# MCU.net
KiCad netlist of a schematic drawn in Altium Designer
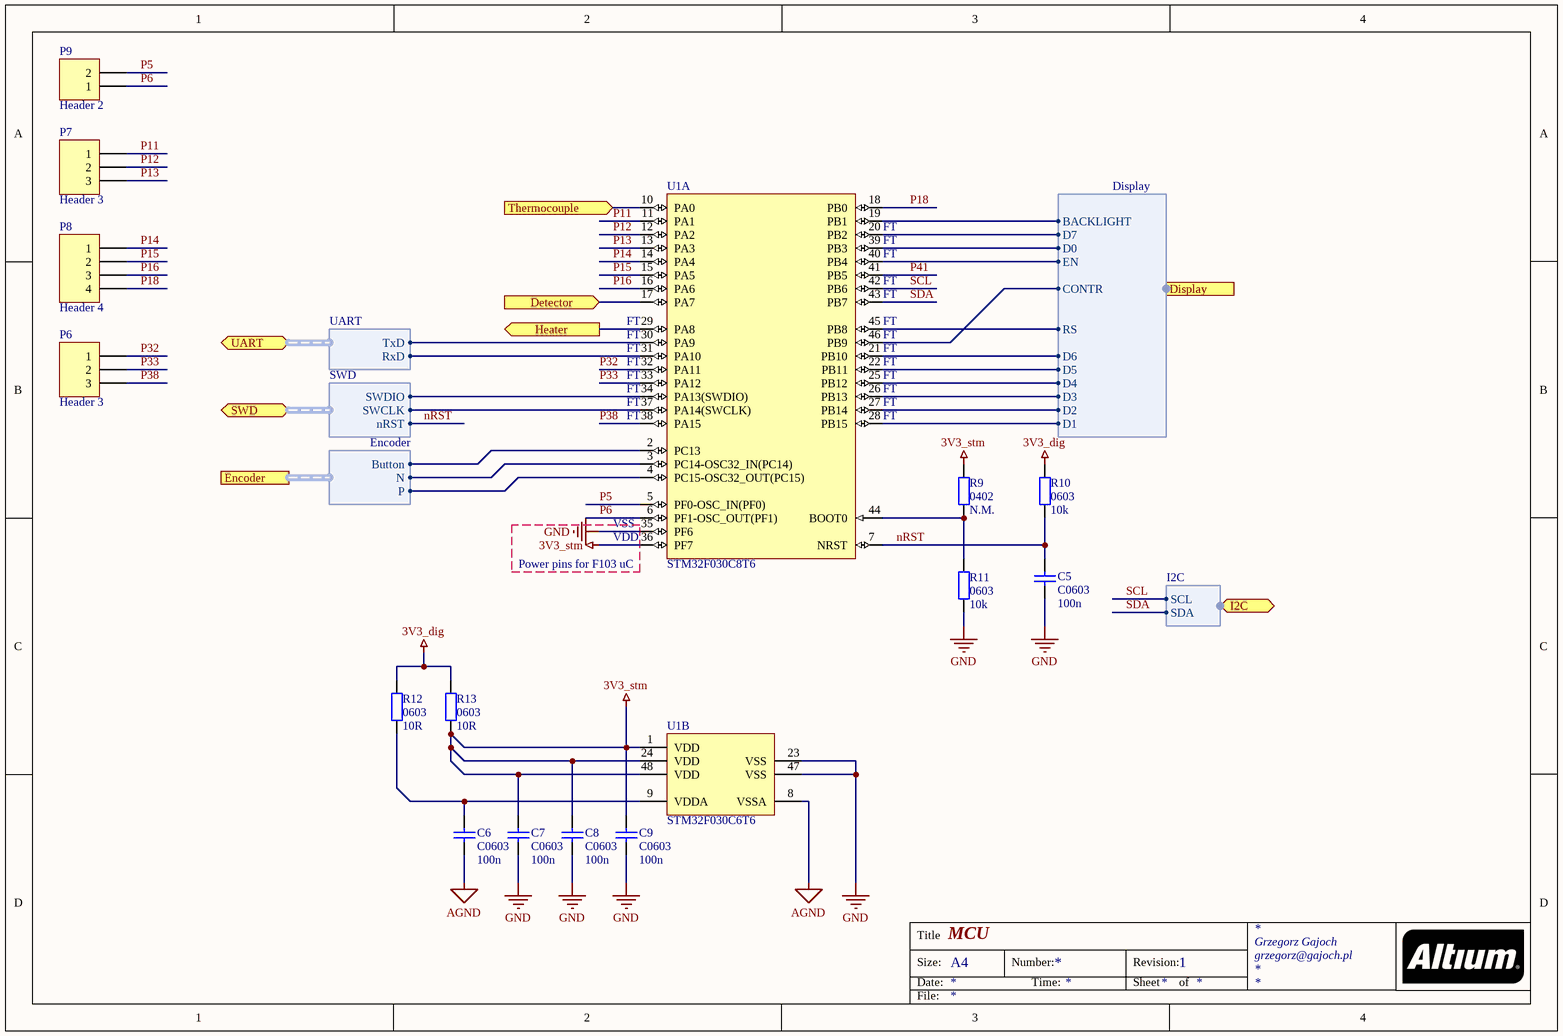
[diagram p0: MCU.SchDoc]

(export (version "E")
  (design (tool "Eeschema 10.0.6"))
  (components
    (comp (ref "C5")
      (value "100n")
      (footprint "C0603")
      (description "Generic capacitor")
      (libsource (lib "_RLC") (part "Cap"))
    )
    (comp (ref "C6")
      (value "100n")
      (footprint "C0603")
      (description "Generic capacitor")
      (libsource (lib "_RLC") (part "Cap"))
    )
    (comp (ref "C7")
      (value "100n")
      (footprint "C0603")
      (description "Generic capacitor")
      (libsource (lib "_RLC") (part "Cap"))
    )
    (comp (ref "C8")
      (value "100n")
      (footprint "C0603")
      (description "Generic capacitor")
      (libsource (lib "_RLC") (part "Cap"))
    )
    (comp (ref "C9")
      (value "100n")
      (footprint "C0603")
      (description "Generic capacitor")
      (libsource (lib "_RLC") (part "Cap"))
    )
    (comp (ref "P6")
      (value "Header 3")
      (footprint "HEADER 1X3 MALE")
      (description "Header, 3-Pin")
      (fields (field (name "PUBLISHER") "Altium Limited"))
      (libsource (lib "_Connectors") (part "Header 3"))
    )
    (comp (ref "P7")
      (value "Header 3")
      (footprint "HEADER 1X3 MALE")
      (description "Header, 3-Pin")
      (fields (field (name "PUBLISHER") "Altium Limited"))
      (libsource (lib "_Connectors") (part "Header 3"))
    )
    (comp (ref "P8")
      (value "Header 4")
      (footprint "HEADER 1x4 MALE")
      (description "Header, 4-Pin")
      (fields (field (name "PUBLISHER") "Altium Limited"))
      (libsource (lib "_Connectors") (part "Header 4"))
    )
    (comp (ref "P9")
      (value "Header 2")
      (footprint "HEADER 1X2 Male")
      (description "Header, 2-Pin")
      (fields (field (name "PUBLISHER") "Altium Limited"))
      (libsource (lib "_Connectors") (part "Header 2"))
    )
    (comp (ref "R9")
      (value "N.M.")
      (footprint "0402")
      (description "Generic resistor")
      (libsource (lib "_RLC") (part "Res"))
    )
    (comp (ref "R10")
      (value "10k")
      (footprint "0603")
      (description "Generic resistor")
      (libsource (lib "_RLC") (part "Res"))
    )
    (comp (ref "R11")
      (value "10k")
      (footprint "0603")
      (description "Generic resistor")
      (libsource (lib "_RLC") (part "Res"))
    )
    (comp (ref "R12")
      (value "10R")
      (footprint "0603")
      (description "Generic resistor")
      (libsource (lib "_RLC") (part "Res"))
    )
    (comp (ref "R13")
      (value "10R")
      (footprint "0603")
      (description "Generic resistor")
      (libsource (lib "_RLC") (part "Res"))
    )
    (comp (ref "U1")
      (value "STM32F030C8T6")
      (footprint "QFP_48_0.5_M")
      (fields (field (name "PARTNUMBER") "STM32F030C6T6"))
      (libsource (lib "_Microcircuits") (part "STM32F030C6T6"))
    )
  )
  (nets
    (net (code "6") (name "/BACKLIGHT") (class "Default")
      (node (ref "U1") (pin "19") (pinfunction "PB1_19") (pintype "bidirectional"))
    )
    (net (code "7") (name "/Button") (class "Default")
      (node (ref "U1") (pin "2") (pinfunction "PC13_2") (pintype "bidirectional"))
    )
    (net (code "8") (name "/CONTR") (class "Default")
      (node (ref "U1") (pin "46") (pinfunction "PB9_46") (pintype "bidirectional"))
    )
    (net (code "9") (name "/D0") (class "Default")
      (node (ref "U1") (pin "39") (pinfunction "PB3_39") (pintype "bidirectional"))
    )
    (net (code "10") (name "/D1") (class "Default")
      (node (ref "U1") (pin "28") (pinfunction "PB15_28") (pintype "bidirectional"))
    )
    (net (code "11") (name "/D2") (class "Default")
      (node (ref "U1") (pin "27") (pinfunction "PB14_27") (pintype "bidirectional"))
    )
    (net (code "12") (name "/D3") (class "Default")
      (node (ref "U1") (pin "26") (pinfunction "PB13_26") (pintype "bidirectional"))
    )
    (net (code "13") (name "/D4") (class "Default")
      (node (ref "U1") (pin "25") (pinfunction "PB12_25") (pintype "bidirectional"))
    )
    (net (code "14") (name "/D5") (class "Default")
      (node (ref "U1") (pin "22") (pinfunction "PB11_22") (pintype "bidirectional"))
    )
    (net (code "15") (name "/D6") (class "Default")
      (node (ref "U1") (pin "21") (pinfunction "PB10_21") (pintype "bidirectional"))
    )
    (net (code "16") (name "/D7") (class "Default")
      (node (ref "U1") (pin "20") (pinfunction "PB2_20") (pintype "bidirectional"))
    )
    (net (code "17") (name "/Detector") (class "Default")
      (node (ref "U1") (pin "17") (pinfunction "PA7_17") (pintype "bidirectional"))
    )
    (net (code "18") (name "/EN") (class "Default")
      (node (ref "U1") (pin "40") (pinfunction "PB4_40") (pintype "bidirectional"))
    )
    (net (code "19") (name "/Heater") (class "Default")
      (node (ref "U1") (pin "29") (pinfunction "PA8_29") (pintype "bidirectional"))
    )
    (net (code "20") (name "/N") (class "Default")
      (node (ref "U1") (pin "3") (pinfunction "PC14-OSC32_IN(PC14)_3") (pintype "bidirectional"))
    )
    (net (code "21") (name "/P") (class "Default")
      (node (ref "U1") (pin "4") (pinfunction "PC15-OSC32_OUT(PC15)_4") (pintype "bidirectional"))
    )
    (net (code "22") (name "/P5") (class "Default")
      (node (ref "P9") (pin "2") (pinfunction "2_2") (pintype "passive"))
      (node (ref "U1") (pin "5") (pinfunction "PF0-OSC_IN(PF0)_5") (pintype "bidirectional"))
    )
    (net (code "23") (name "/P6") (class "Default")
      (node (ref "P9") (pin "1") (pinfunction "1_1") (pintype "passive"))
      (node (ref "U1") (pin "6") (pinfunction "PF1-OSC_OUT(PF1)_6") (pintype "bidirectional"))
    )
    (net (code "24") (name "/P11") (class "Default")
      (node (ref "P7") (pin "1") (pinfunction "1_1") (pintype "passive"))
      (node (ref "U1") (pin "11") (pinfunction "PA1_11") (pintype "bidirectional"))
    )
    (net (code "25") (name "/P12") (class "Default")
      (node (ref "P7") (pin "2") (pinfunction "2_2") (pintype "passive"))
      (node (ref "U1") (pin "12") (pinfunction "PA2_12") (pintype "bidirectional"))
    )
    (net (code "26") (name "/P13") (class "Default")
      (node (ref "P7") (pin "3") (pinfunction "3_3") (pintype "passive"))
      (node (ref "U1") (pin "13") (pinfunction "PA3_13") (pintype "bidirectional"))
    )
    (net (code "27") (name "/P14") (class "Default")
      (node (ref "P8") (pin "1") (pinfunction "1_1") (pintype "passive"))
      (node (ref "U1") (pin "14") (pinfunction "PA4_14") (pintype "bidirectional"))
    )
    (net (code "28") (name "/P15") (class "Default")
      (node (ref "P8") (pin "2") (pinfunction "2_2") (pintype "passive"))
      (node (ref "U1") (pin "15") (pinfunction "PA5_15") (pintype "bidirectional"))
    )
    (net (code "29") (name "/P16") (class "Default")
      (node (ref "P8") (pin "3") (pinfunction "3_3") (pintype "passive"))
      (node (ref "U1") (pin "16") (pinfunction "PA6_16") (pintype "bidirectional"))
    )
    (net (code "30") (name "/P18") (class "Default")
      (node (ref "P8") (pin "4") (pinfunction "4_4") (pintype "passive"))
      (node (ref "U1") (pin "18") (pinfunction "PB0_18") (pintype "bidirectional"))
    )
    (net (code "31") (name "/P32") (class "Default")
      (node (ref "P6") (pin "1") (pinfunction "1_1") (pintype "passive"))
      (node (ref "U1") (pin "32") (pinfunction "PA11_32") (pintype "bidirectional"))
    )
    (net (code "32") (name "/P33") (class "Default")
      (node (ref "P6") (pin "2") (pinfunction "2_2") (pintype "passive"))
      (node (ref "U1") (pin "33") (pinfunction "PA12_33") (pintype "bidirectional"))
    )
    (net (code "33") (name "/P38") (class "Default")
      (node (ref "P6") (pin "3") (pinfunction "3_3") (pintype "passive"))
      (node (ref "U1") (pin "38") (pinfunction "PA15_38") (pintype "bidirectional"))
    )
    (net (code "34") (name "/P41") (class "Default")
      (node (ref "U1") (pin "41") (pinfunction "PB5_41") (pintype "bidirectional"))
    )
    (net (code "35") (name "/RS") (class "Default")
      (node (ref "U1") (pin "45") (pinfunction "PB8_45") (pintype "bidirectional"))
    )
    (net (code "36") (name "/RxD") (class "Default")
      (node (ref "U1") (pin "31") (pinfunction "PA10_31") (pintype "bidirectional"))
    )
    (net (code "37") (name "/SCL") (class "Default")
      (node (ref "U1") (pin "42") (pinfunction "PB6_42") (pintype "bidirectional"))
    )
    (net (code "38") (name "/SDA") (class "Default")
      (node (ref "U1") (pin "43") (pinfunction "PB7_43") (pintype "bidirectional"))
    )
    (net (code "39") (name "/SWCLK") (class "Default")
      (node (ref "U1") (pin "37") (pinfunction "PA14(SWCLK)_37") (pintype "bidirectional"))
    )
    (net (code "40") (name "/SWDIO") (class "Default")
      (node (ref "U1") (pin "34") (pinfunction "PA13(SWDIO)_34") (pintype "bidirectional"))
    )
    (net (code "41") (name "/Thermocouple") (class "Default")
      (node (ref "U1") (pin "10") (pinfunction "PA0_10") (pintype "bidirectional"))
    )
    (net (code "42") (name "/TxD") (class "Default")
      (node (ref "U1") (pin "30") (pinfunction "PA9_30") (pintype "bidirectional"))
    )
    (net (code "43") (name "/nRST") (class "Default")
      (node (ref "C5") (pin "1") (pinfunction "1_1") (pintype "passive"))
      (node (ref "R10") (pin "2") (pinfunction "2_2") (pintype "passive"))
      (node (ref "U1") (pin "7") (pinfunction "NRST_7") (pintype "bidirectional"))
    )
    (net (code "49") (name "3V3_dig") (class "Default")
      (node (ref "R10") (pin "1") (pinfunction "1_1") (pintype "passive"))
      (node (ref "R12") (pin "1") (pinfunction "1_1") (pintype "passive"))
      (node (ref "R13") (pin "1") (pinfunction "1_1") (pintype "passive"))
    )
    (net (code "50") (name "3V3_stm") (class "Default")
      (node (ref "C7") (pin "1") (pinfunction "1_1") (pintype "passive"))
      (node (ref "C8") (pin "1") (pinfunction "1_1") (pintype "passive"))
      (node (ref "C9") (pin "1") (pinfunction "1_1") (pintype "passive"))
      (node (ref "R13") (pin "2") (pinfunction "2_2") (pintype "passive"))
      (node (ref "R9") (pin "1") (pinfunction "1_1") (pintype "passive"))
      (node (ref "U1") (pin "1") (pinfunction "VDD_1") (pintype "power_in"))
      (node (ref "U1") (pin "24") (pinfunction "VDD_24") (pintype "power_in"))
      (node (ref "U1") (pin "36") (pinfunction "PF7_36") (pintype "bidirectional"))
      (node (ref "U1") (pin "48") (pinfunction "VDD_48") (pintype "power_in"))
    )
    (net (code "51") (name "AGND") (class "Default")
      (node (ref "C6") (pin "2") (pinfunction "2_2") (pintype "passive"))
      (node (ref "U1") (pin "8") (pinfunction "VSSA_8") (pintype "power_in"))
    )
    (net (code "52") (name "GND") (class "Default")
      (node (ref "C5") (pin "2") (pinfunction "2_2") (pintype "passive"))
      (node (ref "C7") (pin "2") (pinfunction "2_2") (pintype "passive"))
      (node (ref "C8") (pin "2") (pinfunction "2_2") (pintype "passive"))
      (node (ref "C9") (pin "2") (pinfunction "2_2") (pintype "passive"))
      (node (ref "R11") (pin "2") (pinfunction "2_2") (pintype "passive"))
      (node (ref "U1") (pin "23") (pinfunction "VSS_23") (pintype "power_in"))
      (node (ref "U1") (pin "35") (pinfunction "PF6_35") (pintype "bidirectional"))
      (node (ref "U1") (pin "47") (pinfunction "VSS_47") (pintype "power_in"))
    )
    (net (code "53") (name "Net-(U1A-BOOT0)") (class "Default")
      (node (ref "R11") (pin "1") (pinfunction "1_1") (pintype "passive"))
      (node (ref "R9") (pin "2") (pinfunction "2_2") (pintype "passive"))
      (node (ref "U1") (pin "44") (pinfunction "BOOT0_44") (pintype "input"))
    )
    (net (code "54") (name "Net-(U1B-VDDA)") (class "Default")
      (node (ref "C6") (pin "1") (pinfunction "1_1") (pintype "passive"))
      (node (ref "R12") (pin "2") (pinfunction "2_2") (pintype "passive"))
      (node (ref "U1") (pin "9") (pinfunction "VDDA_9") (pintype "power_in"))
    )
  )
)
